# avr_g1000_ctr_24.net
KiCad netlist of a schematic drawn in EAGLE
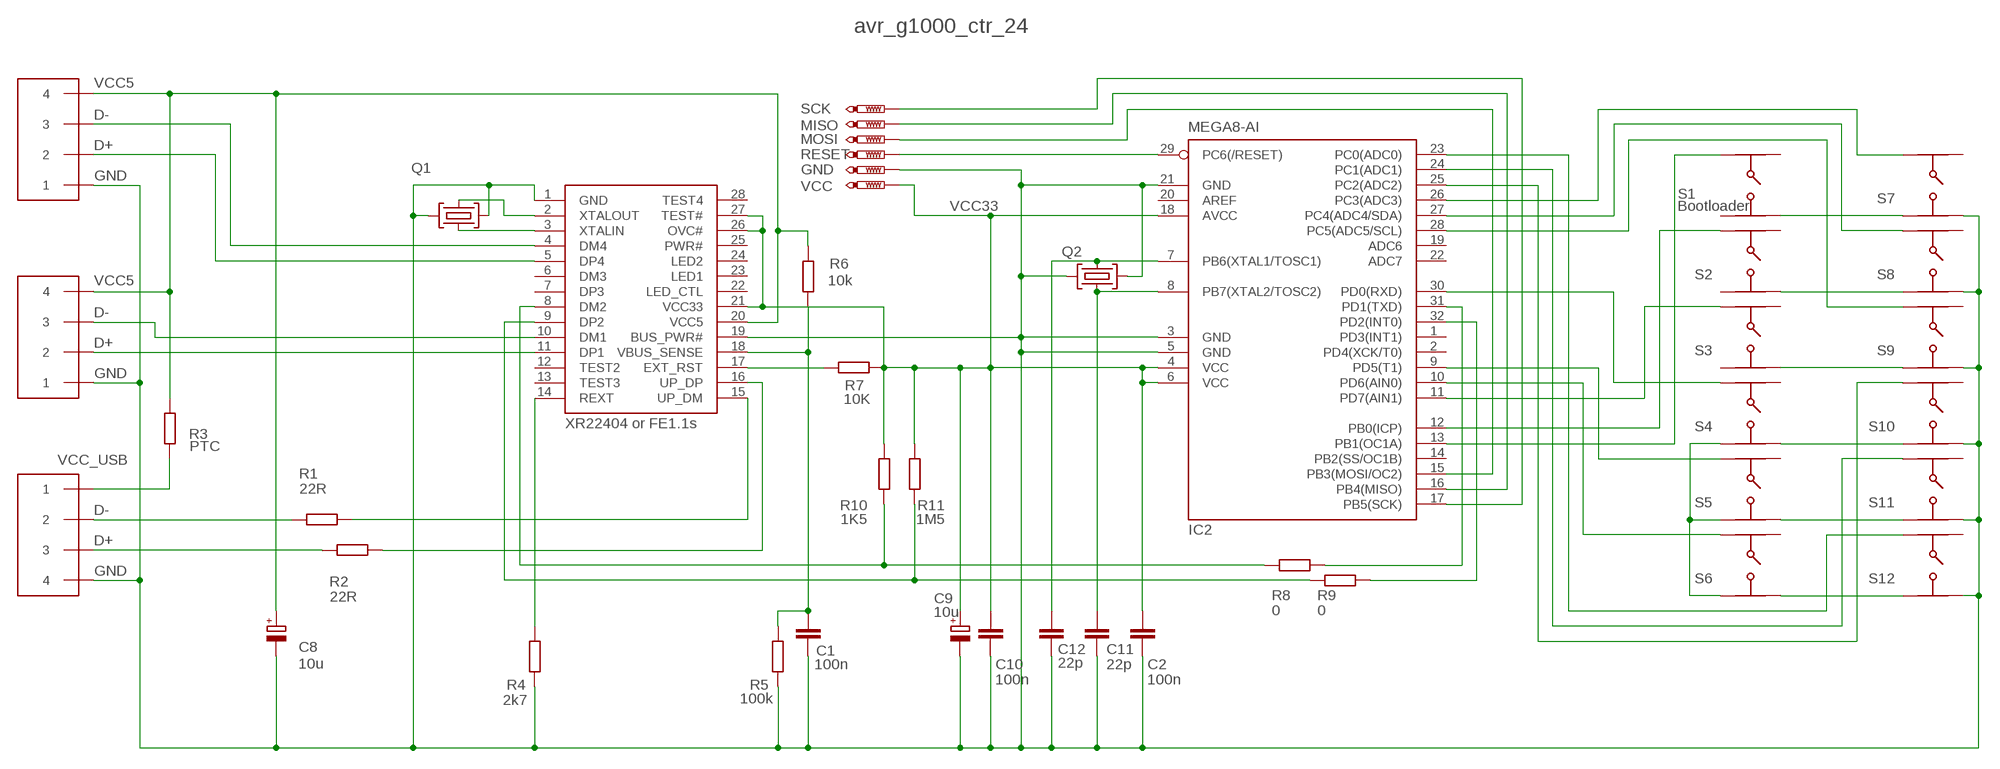
[diagram p0: schematic, sheet 1]

(export (version "E")
  (design (tool "Eeschema 10.0.6"))
  (components
    (comp (ref "C1")
      (value "100n")
      (footprint "eagle-import:C0402")
      (libsource (lib "eagle-import") (part "C-EUC0402"))
    )
    (comp (ref "C2")
      (value "100n")
      (footprint "eagle-import:C0402")
      (libsource (lib "eagle-import") (part "C-EUC0402"))
    )
    (comp (ref "C8")
      (value "10u")
      (footprint "eagle-import:SMC_A")
      (libsource (lib "eagle-import") (part "CPOL-EUSMCA"))
    )
    (comp (ref "C9")
      (value "10u")
      (footprint "eagle-import:SMC_A")
      (libsource (lib "eagle-import") (part "CPOL-EUSMCA"))
    )
    (comp (ref "C10")
      (value "100n")
      (footprint "eagle-import:C0402")
      (libsource (lib "eagle-import") (part "C-EUC0402"))
    )
    (comp (ref "C11")
      (value "22p")
      (footprint "eagle-import:C0402")
      (libsource (lib "eagle-import") (part "C-EUC0402"))
    )
    (comp (ref "C12")
      (value "22p")
      (footprint "eagle-import:C0402")
      (libsource (lib "eagle-import") (part "C-EUC0402"))
    )
    (comp (ref "GND")
      (value "PTR1TP10R")
      (footprint "eagle-import:TP10R")
      (libsource (lib "eagle-import") (part "PTR1TP10R"))
    )
    (comp (ref "IC2")
      (value "MEGA8-AI")
      (footprint "eagle-import:TQFP32-08")
      (fields (field (name "MPN") "ATMEGA8-16AU"))
      (libsource (lib "eagle-import") (part "MEGA8-AI"))
    )
    (comp (ref "MISO")
      (value "PTR1TP10R")
      (footprint "eagle-import:TP10R")
      (libsource (lib "eagle-import") (part "PTR1TP10R"))
    )
    (comp (ref "MOSI")
      (value "PTR1TP10R")
      (footprint "eagle-import:TP10R")
      (libsource (lib "eagle-import") (part "PTR1TP10R"))
    )
    (comp (ref "Q1")
      (value "12MHz")
      (footprint "eagle-import:OSCCC500X320X100")
      (libsource (lib "eagle-import") (part "MJ-CRYSTALMJ"))
    )
    (comp (ref "Q2")
      (value "12Mhz")
      (footprint "eagle-import:OSCCC500X320X100")
      (libsource (lib "eagle-import") (part "MJ-CRYSTALMJ"))
    )
    (comp (ref "R1")
      (value "22R")
      (footprint "eagle-import:R0603")
      (libsource (lib "eagle-import") (part "R-EU_R0603"))
    )
    (comp (ref "R2")
      (value "22R")
      (footprint "eagle-import:R0603")
      (libsource (lib "eagle-import") (part "R-EU_R0603"))
    )
    (comp (ref "R3")
      (value "PTC")
      (footprint "eagle-import:R0805")
      (libsource (lib "eagle-import") (part "R-EU_R0805"))
    )
    (comp (ref "R4")
      (value "2k7")
      (footprint "eagle-import:R0603")
      (libsource (lib "eagle-import") (part "R-EU_R0603"))
    )
    (comp (ref "R5")
      (value "100k")
      (footprint "eagle-import:R0603")
      (libsource (lib "eagle-import") (part "R-EU_R0603"))
    )
    (comp (ref "R6")
      (value "10k")
      (footprint "eagle-import:R0603")
      (libsource (lib "eagle-import") (part "R-EU_R0603"))
    )
    (comp (ref "R7")
      (value "10K")
      (footprint "eagle-import:R0603")
      (libsource (lib "eagle-import") (part "R-EU_R0603"))
    )
    (comp (ref "R8")
      (value "0")
      (footprint "eagle-import:R0603")
      (libsource (lib "eagle-import") (part "R-EU_R0603"))
    )
    (comp (ref "R9")
      (value "0")
      (footprint "eagle-import:R0603")
      (libsource (lib "eagle-import") (part "R-EU_R0603"))
    )
    (comp (ref "R10")
      (value "1K5")
      (footprint "eagle-import:R0603")
      (libsource (lib "eagle-import") (part "R-EU_R0603"))
    )
    (comp (ref "R11")
      (value "1M5")
      (footprint "eagle-import:R0603")
      (libsource (lib "eagle-import") (part "R-EU_R0603"))
    )
    (comp (ref "RESET")
      (value "PTR1TP10R")
      (footprint "eagle-import:TP10R")
      (libsource (lib "eagle-import") (part "PTR1TP10R"))
    )
    (comp (ref "S1")
      (value "B3FS1000")
      (footprint "eagle-import:B3FS1000")
      (libsource (lib "eagle-import") (part "B3FS1000"))
    )
    (comp (ref "S2")
      (value "B3FS1000")
      (footprint "eagle-import:B3FS1000")
      (libsource (lib "eagle-import") (part "B3FS1000"))
    )
    (comp (ref "S3")
      (value "B3FS1000")
      (footprint "eagle-import:B3FS1000")
      (libsource (lib "eagle-import") (part "B3FS1000"))
    )
    (comp (ref "S4")
      (value "B3FS1000")
      (footprint "eagle-import:B3FS1000")
      (libsource (lib "eagle-import") (part "B3FS1000"))
    )
    (comp (ref "S5")
      (value "B3FS1000")
      (footprint "eagle-import:B3FS1000")
      (libsource (lib "eagle-import") (part "B3FS1000"))
    )
    (comp (ref "S6")
      (value "B3FS1000")
      (footprint "eagle-import:B3FS1000")
      (libsource (lib "eagle-import") (part "B3FS1000"))
    )
    (comp (ref "S7")
      (value "B3FS1000")
      (footprint "eagle-import:B3FS1000")
      (libsource (lib "eagle-import") (part "B3FS1000"))
    )
    (comp (ref "S8")
      (value "B3FS1000")
      (footprint "eagle-import:B3FS1000")
      (libsource (lib "eagle-import") (part "B3FS1000"))
    )
    (comp (ref "S9")
      (value "B3FS1000")
      (footprint "eagle-import:B3FS1000")
      (libsource (lib "eagle-import") (part "B3FS1000"))
    )
    (comp (ref "S10")
      (value "B3FS1000")
      (footprint "eagle-import:B3FS1000")
      (libsource (lib "eagle-import") (part "B3FS1000"))
    )
    (comp (ref "S11")
      (value "B3FS1000")
      (footprint "eagle-import:B3FS1000")
      (libsource (lib "eagle-import") (part "B3FS1000"))
    )
    (comp (ref "S12")
      (value "B3FS1000")
      (footprint "eagle-import:B3FS1000")
      (libsource (lib "eagle-import") (part "B3FS1000"))
    )
    (comp (ref "SCK")
      (value "PTR1TP10R")
      (footprint "eagle-import:TP10R")
      (libsource (lib "eagle-import") (part "PTR1TP10R"))
    )
    (comp (ref "U$1")
      (value "HEADER4X1.27")
      (footprint "eagle-import:HEADER4X1.27")
      (libsource (lib "eagle-import") (part "HEADER4X1.27"))
    )
    (comp (ref "U$2")
      (value "HEADER4X1.27")
      (footprint "eagle-import:HEADER4X1.27")
      (libsource (lib "eagle-import") (part "HEADER4X1.27"))
    )
    (comp (ref "U$3")
      (value "HEADER4X1.27")
      (footprint "eagle-import:HEADER4X1.27")
      (libsource (lib "eagle-import") (part "HEADER4X1.27"))
    )
    (comp (ref "VCC")
      (value "PTR1TP10R")
      (footprint "eagle-import:TP10R")
      (libsource (lib "eagle-import") (part "PTR1TP10R"))
    )
    (comp (ref "XR22404")
      (value "XR22404")
      (footprint "eagle-import:XR22404")
      (libsource (lib "eagle-import") (part "XR22404"))
    )
  )
  (nets
    (net (code "1") (name "/D+") (class "Default")
      (node (ref "R2") (pin "1") (pinfunction "1_1") (pintype "passive"))
      (node (ref "U$1") (pin "P3") (pinfunction "3_P3") (pintype "bidirectional"))
    )
    (net (code "2") (name "/D-") (class "Default")
      (node (ref "R1") (pin "1") (pinfunction "1_1") (pintype "passive"))
      (node (ref "U$1") (pin "P2") (pinfunction "2_P2") (pintype "bidirectional"))
    )
    (net (code "3") (name "/GND") (class "Default")
      (node (ref "C1") (pin "2") (pinfunction "2_2") (pintype "passive"))
      (node (ref "C10") (pin "2") (pinfunction "2_2") (pintype "passive"))
      (node (ref "C11") (pin "2") (pinfunction "2_2") (pintype "passive"))
      (node (ref "C12") (pin "2") (pinfunction "2_2") (pintype "passive"))
      (node (ref "C2") (pin "2") (pinfunction "2_2") (pintype "passive"))
      (node (ref "C8") (pin "-") (pinfunction "-_-") (pintype "passive"))
      (node (ref "C9") (pin "-") (pinfunction "-_-") (pintype "passive"))
      (node (ref "GND") (pin "TP") (pinfunction "TP_TP") (pintype "input"))
      (node (ref "IC2") (pin "21") (pinfunction "GND_21") (pintype "power_in"))
      (node (ref "IC2") (pin "3") (pinfunction "GND_3") (pintype "power_in"))
      (node (ref "IC2") (pin "5") (pinfunction "GND_5") (pintype "power_in"))
      (node (ref "Q1") (pin "2") (pinfunction "GND1_2") (pintype "bidirectional"))
      (node (ref "Q1") (pin "4") (pinfunction "GND2_4") (pintype "bidirectional"))
      (node (ref "Q2") (pin "2") (pinfunction "GND1_2") (pintype "bidirectional"))
      (node (ref "Q2") (pin "4") (pinfunction "GND2_4") (pintype "bidirectional"))
      (node (ref "R4") (pin "1") (pinfunction "1_1") (pintype "passive"))
      (node (ref "R5") (pin "1") (pinfunction "1_1") (pintype "passive"))
      (node (ref "S1") (pin "1") (pinfunction "1_1") (pintype "passive"))
      (node (ref "S10") (pin "1") (pinfunction "1_1") (pintype "passive"))
      (node (ref "S10") (pin "2") (pinfunction "2_2") (pintype "passive"))
      (node (ref "S11") (pin "1") (pinfunction "1_1") (pintype "passive"))
      (node (ref "S11") (pin "2") (pinfunction "2_2") (pintype "passive"))
      (node (ref "S12") (pin "1") (pinfunction "1_1") (pintype "passive"))
      (node (ref "S12") (pin "2") (pinfunction "2_2") (pintype "passive"))
      (node (ref "S2") (pin "1") (pinfunction "1_1") (pintype "passive"))
      (node (ref "S3") (pin "1") (pinfunction "1_1") (pintype "passive"))
      (node (ref "S4") (pin "1") (pinfunction "1_1") (pintype "passive"))
      (node (ref "S4") (pin "2") (pinfunction "2_2") (pintype "passive"))
      (node (ref "S5") (pin "1") (pinfunction "1_1") (pintype "passive"))
      (node (ref "S5") (pin "2") (pinfunction "2_2") (pintype "passive"))
      (node (ref "S6") (pin "1") (pinfunction "1_1") (pintype "passive"))
      (node (ref "S6") (pin "2") (pinfunction "2_2") (pintype "passive"))
      (node (ref "S7") (pin "1") (pinfunction "1_1") (pintype "passive"))
      (node (ref "S7") (pin "2") (pinfunction "2_2") (pintype "passive"))
      (node (ref "S8") (pin "1") (pinfunction "1_1") (pintype "passive"))
      (node (ref "S8") (pin "2") (pinfunction "2_2") (pintype "passive"))
      (node (ref "S9") (pin "1") (pinfunction "1_1") (pintype "passive"))
      (node (ref "S9") (pin "2") (pinfunction "2_2") (pintype "passive"))
      (node (ref "U$1") (pin "P4") (pinfunction "4_P4") (pintype "bidirectional"))
      (node (ref "U$2") (pin "P1") (pinfunction "1_P1") (pintype "bidirectional"))
      (node (ref "U$3") (pin "P1") (pinfunction "1_P1") (pintype "bidirectional"))
      (node (ref "XR22404") (pin "1") (pinfunction "GND_1") (pintype "passive"))
      (node (ref "XR22404") (pin "19") (pinfunction "BUS_PWR#_19") (pintype "bidirectional"))
    )
    (net (code "4") (name "/VCC5") (class "Default")
      (node (ref "C8") (pin "+") (pinfunction "+_+") (pintype "passive"))
      (node (ref "R3") (pin "2") (pinfunction "2_2") (pintype "passive"))
      (node (ref "R6") (pin "2") (pinfunction "2_2") (pintype "passive"))
      (node (ref "U$2") (pin "P4") (pinfunction "4_P4") (pintype "bidirectional"))
      (node (ref "U$3") (pin "P4") (pinfunction "4_P4") (pintype "bidirectional"))
      (node (ref "XR22404") (pin "20") (pinfunction "VCC5_20") (pintype "bidirectional"))
    )
    (net (code "5") (name "/VCC33") (class "Default")
      (node (ref "C10") (pin "1") (pinfunction "1_1") (pintype "passive"))
      (node (ref "C2") (pin "1") (pinfunction "1_1") (pintype "passive"))
      (node (ref "C9") (pin "+") (pinfunction "+_+") (pintype "passive"))
      (node (ref "IC2") (pin "18") (pinfunction "AVCC_18") (pintype "power_in"))
      (node (ref "IC2") (pin "4") (pinfunction "VCC_4") (pintype "power_in"))
      (node (ref "IC2") (pin "6") (pinfunction "VCC_6") (pintype "power_in"))
      (node (ref "R10") (pin "2") (pinfunction "2_2") (pintype "passive"))
      (node (ref "R11") (pin "2") (pinfunction "2_2") (pintype "passive"))
      (node (ref "R7") (pin "2") (pinfunction "2_2") (pintype "passive"))
      (node (ref "VCC") (pin "TP") (pinfunction "TP_TP") (pintype "input"))
      (node (ref "XR22404") (pin "21") (pinfunction "VCC33_21") (pintype "bidirectional"))
      (node (ref "XR22404") (pin "26") (pinfunction "OVC#_26") (pintype "bidirectional"))
      (node (ref "XR22404") (pin "27") (pinfunction "TEST#_27") (pintype "bidirectional"))
    )
    (net (code "6") (name "/VCC_USB") (class "Default")
      (node (ref "R3") (pin "1") (pinfunction "1_1") (pintype "passive"))
      (node (ref "U$1") (pin "P1") (pinfunction "1_P1") (pintype "bidirectional"))
    )
    (net (code "7") (name "Net-(IC2-PB0(ICP))") (class "Default")
      (node (ref "IC2") (pin "12") (pinfunction "PB0(ICP)_12") (pintype "bidirectional"))
      (node (ref "S2") (pin "4") (pinfunction "4_4") (pintype "passive"))
    )
    (net (code "8") (name "Net-(IC2-PB1(OC1A))") (class "Default")
      (node (ref "IC2") (pin "13") (pinfunction "PB1(OC1A)_13") (pintype "bidirectional"))
      (node (ref "S1") (pin "4") (pinfunction "4_4") (pintype "passive"))
    )
    (net (code "9") (name "Net-(IC2-PB3(MOSI{slash}OC2))") (class "Default")
      (node (ref "IC2") (pin "15") (pinfunction "PB3(MOSI/OC2)_15") (pintype "bidirectional"))
      (node (ref "MOSI") (pin "TP") (pinfunction "TP_TP") (pintype "input"))
    )
    (net (code "10") (name "Net-(IC2-PB4(MISO))") (class "Default")
      (node (ref "IC2") (pin "16") (pinfunction "PB4(MISO)_16") (pintype "bidirectional"))
      (node (ref "MISO") (pin "TP") (pinfunction "TP_TP") (pintype "input"))
    )
    (net (code "11") (name "Net-(IC2-PB5(SCK))") (class "Default")
      (node (ref "IC2") (pin "17") (pinfunction "PB5(SCK)_17") (pintype "bidirectional"))
      (node (ref "SCK") (pin "TP") (pinfunction "TP_TP") (pintype "input"))
    )
    (net (code "12") (name "Net-(IC2-PB6(XTAL1{slash}TOSC1))") (class "Default")
      (node (ref "C12") (pin "1") (pinfunction "1_1") (pintype "passive"))
      (node (ref "IC2") (pin "7") (pinfunction "PB6(XTAL1/TOSC1)_7") (pintype "bidirectional"))
      (node (ref "Q2") (pin "1") (pinfunction "CRYSTAL1_1") (pintype "bidirectional"))
    )
    (net (code "13") (name "Net-(IC2-PB7(XTAL2{slash}TOSC2))") (class "Default")
      (node (ref "C11") (pin "1") (pinfunction "1_1") (pintype "passive"))
      (node (ref "IC2") (pin "8") (pinfunction "PB7(XTAL2/TOSC2)_8") (pintype "bidirectional"))
      (node (ref "Q2") (pin "3") (pinfunction "CRYSTAL2_3") (pintype "bidirectional"))
    )
    (net (code "14") (name "Net-(IC2-PC0(ADC0))") (class "Default")
      (node (ref "IC2") (pin "23") (pinfunction "PC0(ADC0)_23") (pintype "bidirectional"))
      (node (ref "S12") (pin "4") (pinfunction "4_4") (pintype "passive"))
    )
    (net (code "15") (name "Net-(IC2-PC1(ADC1))") (class "Default")
      (node (ref "IC2") (pin "24") (pinfunction "PC1(ADC1)_24") (pintype "bidirectional"))
      (node (ref "S11") (pin "4") (pinfunction "4_4") (pintype "passive"))
    )
    (net (code "16") (name "Net-(IC2-PC2(ADC2))") (class "Default")
      (node (ref "IC2") (pin "25") (pinfunction "PC2(ADC2)_25") (pintype "bidirectional"))
      (node (ref "S10") (pin "4") (pinfunction "4_4") (pintype "passive"))
    )
    (net (code "17") (name "Net-(IC2-PC3(ADC3))") (class "Default")
      (node (ref "IC2") (pin "26") (pinfunction "PC3(ADC3)_26") (pintype "bidirectional"))
      (node (ref "S7") (pin "4") (pinfunction "4_4") (pintype "passive"))
    )
    (net (code "18") (name "Net-(IC2-PC4(ADC4{slash}SDA))") (class "Default")
      (node (ref "IC2") (pin "27") (pinfunction "PC4(ADC4/SDA)_27") (pintype "bidirectional"))
      (node (ref "S8") (pin "4") (pinfunction "4_4") (pintype "passive"))
    )
    (net (code "19") (name "Net-(IC2-PC5(ADC5{slash}SCL))") (class "Default")
      (node (ref "IC2") (pin "28") (pinfunction "PC5(ADC5/SCL)_28") (pintype "bidirectional"))
      (node (ref "S9") (pin "4") (pinfunction "4_4") (pintype "passive"))
    )
    (net (code "20") (name "Net-(IC2-PC6({slash}RESET))") (class "Default")
      (node (ref "IC2") (pin "29") (pinfunction "PC6(/RESET)_29") (pintype "bidirectional"))
      (node (ref "RESET") (pin "TP") (pinfunction "TP_TP") (pintype "input"))
    )
    (net (code "21") (name "Net-(IC2-PD0(RXD))") (class "Default")
      (node (ref "IC2") (pin "30") (pinfunction "PD0(RXD)_30") (pintype "bidirectional"))
      (node (ref "S4") (pin "4") (pinfunction "4_4") (pintype "passive"))
    )
    (net (code "22") (name "Net-(IC2-PD1(TXD))") (class "Default")
      (node (ref "IC2") (pin "31") (pinfunction "PD1(TXD)_31") (pintype "bidirectional"))
      (node (ref "R8") (pin "2") (pinfunction "2_2") (pintype "passive"))
    )
    (net (code "23") (name "Net-(IC2-PD2(INT0))") (class "Default")
      (node (ref "IC2") (pin "32") (pinfunction "PD2(INT0)_32") (pintype "bidirectional"))
      (node (ref "R9") (pin "2") (pinfunction "2_2") (pintype "passive"))
    )
    (net (code "24") (name "Net-(IC2-PD5(T1))") (class "Default")
      (node (ref "IC2") (pin "9") (pinfunction "PD5(T1)_9") (pintype "bidirectional"))
      (node (ref "S5") (pin "4") (pinfunction "4_4") (pintype "passive"))
    )
    (net (code "25") (name "Net-(IC2-PD6(AIN0))") (class "Default")
      (node (ref "IC2") (pin "10") (pinfunction "PD6(AIN0)_10") (pintype "bidirectional"))
      (node (ref "S6") (pin "4") (pinfunction "4_4") (pintype "passive"))
    )
    (net (code "26") (name "Net-(IC2-PD7(AIN1))") (class "Default")
      (node (ref "IC2") (pin "11") (pinfunction "PD7(AIN1)_11") (pintype "bidirectional"))
      (node (ref "S3") (pin "4") (pinfunction "4_4") (pintype "passive"))
    )
    (net (code "27") (name "Net-(Q1-CRYSTAL1)") (class "Default")
      (node (ref "Q1") (pin "1") (pinfunction "CRYSTAL1_1") (pintype "bidirectional"))
      (node (ref "XR22404") (pin "2") (pinfunction "XTALOUT_2") (pintype "bidirectional"))
    )
    (net (code "28") (name "Net-(Q1-CRYSTAL2)") (class "Default")
      (node (ref "Q1") (pin "3") (pinfunction "CRYSTAL2_3") (pintype "bidirectional"))
      (node (ref "XR22404") (pin "3") (pinfunction "XTALIN_3") (pintype "bidirectional"))
    )
    (net (code "29") (name "Net-(U$2-2)") (class "Default")
      (node (ref "U$2") (pin "P2") (pinfunction "2_P2") (pintype "bidirectional"))
      (node (ref "XR22404") (pin "11") (pinfunction "DP1_11") (pintype "bidirectional"))
    )
    (net (code "30") (name "Net-(U$2-3)") (class "Default")
      (node (ref "U$2") (pin "P3") (pinfunction "3_P3") (pintype "bidirectional"))
      (node (ref "XR22404") (pin "10") (pinfunction "DM1_10") (pintype "bidirectional"))
    )
    (net (code "31") (name "Net-(U$3-2)") (class "Default")
      (node (ref "U$3") (pin "P2") (pinfunction "2_P2") (pintype "bidirectional"))
      (node (ref "XR22404") (pin "5") (pinfunction "DP4_5") (pintype "bidirectional"))
    )
    (net (code "32") (name "Net-(U$3-3)") (class "Default")
      (node (ref "U$3") (pin "P3") (pinfunction "3_P3") (pintype "bidirectional"))
      (node (ref "XR22404") (pin "4") (pinfunction "DM4_4") (pintype "bidirectional"))
    )
    (net (code "33") (name "Net-(XR22404-DM2)") (class "Default")
      (node (ref "R10") (pin "1") (pinfunction "1_1") (pintype "passive"))
      (node (ref "R8") (pin "1") (pinfunction "1_1") (pintype "passive"))
      (node (ref "XR22404") (pin "8") (pinfunction "DM2_8") (pintype "bidirectional"))
    )
    (net (code "34") (name "Net-(XR22404-DP2)") (class "Default")
      (node (ref "R11") (pin "1") (pinfunction "1_1") (pintype "passive"))
      (node (ref "R9") (pin "1") (pinfunction "1_1") (pintype "passive"))
      (node (ref "XR22404") (pin "9") (pinfunction "DP2_9") (pintype "bidirectional"))
    )
    (net (code "35") (name "Net-(XR22404-EXT_RST)") (class "Default")
      (node (ref "R7") (pin "1") (pinfunction "1_1") (pintype "passive"))
      (node (ref "XR22404") (pin "17") (pinfunction "EXT_RST_17") (pintype "bidirectional"))
    )
    (net (code "36") (name "Net-(XR22404-REXT)") (class "Default")
      (node (ref "R4") (pin "2") (pinfunction "2_2") (pintype "passive"))
      (node (ref "XR22404") (pin "14") (pinfunction "REXT_14") (pintype "bidirectional"))
    )
    (net (code "37") (name "Net-(XR22404-UP_DM)") (class "Default")
      (node (ref "R1") (pin "2") (pinfunction "2_2") (pintype "passive"))
      (node (ref "XR22404") (pin "15") (pinfunction "UP_DM_15") (pintype "bidirectional"))
    )
    (net (code "38") (name "Net-(XR22404-UP_DP)") (class "Default")
      (node (ref "R2") (pin "2") (pinfunction "2_2") (pintype "passive"))
      (node (ref "XR22404") (pin "16") (pinfunction "UP_DP_16") (pintype "bidirectional"))
    )
    (net (code "39") (name "Net-(XR22404-VBUS_SENSE)") (class "Default")
      (node (ref "C1") (pin "1") (pinfunction "1_1") (pintype "passive"))
      (node (ref "R5") (pin "2") (pinfunction "2_2") (pintype "passive"))
      (node (ref "R6") (pin "1") (pinfunction "1_1") (pintype "passive"))
      (node (ref "XR22404") (pin "18") (pinfunction "VBUS_SENSE_18") (pintype "bidirectional"))
    )
    (net (code "40") (name "unconnected-(IC2-ADC6-Pad19)") (class "Default")
      (node (ref "IC2") (pin "19") (pinfunction "ADC6_19") (pintype "bidirectional"))
    )
    (net (code "41") (name "unconnected-(IC2-ADC7-Pad22)") (class "Default")
      (node (ref "IC2") (pin "22") (pinfunction "ADC7_22") (pintype "bidirectional"))
    )
    (net (code "42") (name "unconnected-(IC2-AREF-Pad20)") (class "Default")
      (node (ref "IC2") (pin "20") (pinfunction "AREF_20") (pintype "passive"))
    )
    (net (code "43") (name "unconnected-(IC2-PB2(SS{slash}OC1B)-Pad14)") (class "Default")
      (node (ref "IC2") (pin "14") (pinfunction "PB2(SS/OC1B)_14") (pintype "bidirectional"))
    )
    (net (code "44") (name "unconnected-(IC2-PD3(INT1)-Pad1)") (class "Default")
      (node (ref "IC2") (pin "1") (pinfunction "PD3(INT1)_1") (pintype "bidirectional"))
    )
    (net (code "45") (name "unconnected-(IC2-PD4(XCK{slash}T0)-Pad2)") (class "Default")
      (node (ref "IC2") (pin "2") (pinfunction "PD4(XCK/T0)_2") (pintype "bidirectional"))
    )
    (net (code "46") (name "unconnected-(S1-Pad2)") (class "Default")
      (node (ref "S1") (pin "2") (pinfunction "2_2") (pintype "passive"))
    )
    (net (code "47") (name "unconnected-(S1-Pad3)") (class "Default")
      (node (ref "S1") (pin "3") (pinfunction "3_3") (pintype "passive"))
    )
    (net (code "48") (name "unconnected-(S2-Pad2)") (class "Default")
      (node (ref "S2") (pin "2") (pinfunction "2_2") (pintype "passive"))
    )
    (net (code "49") (name "unconnected-(S2-Pad3)") (class "Default")
      (node (ref "S2") (pin "3") (pinfunction "3_3") (pintype "passive"))
    )
    (net (code "50") (name "unconnected-(S3-Pad2)") (class "Default")
      (node (ref "S3") (pin "2") (pinfunction "2_2") (pintype "passive"))
    )
    (net (code "51") (name "unconnected-(S3-Pad3)") (class "Default")
      (node (ref "S3") (pin "3") (pinfunction "3_3") (pintype "passive"))
    )
    (net (code "52") (name "unconnected-(S4-Pad3)") (class "Default")
      (node (ref "S4") (pin "3") (pinfunction "3_3") (pintype "passive"))
    )
    (net (code "53") (name "unconnected-(S5-Pad3)") (class "Default")
      (node (ref "S5") (pin "3") (pinfunction "3_3") (pintype "passive"))
    )
    (net (code "54") (name "unconnected-(S6-Pad3)") (class "Default")
      (node (ref "S6") (pin "3") (pinfunction "3_3") (pintype "passive"))
    )
    (net (code "55") (name "unconnected-(S7-Pad3)") (class "Default")
      (node (ref "S7") (pin "3") (pinfunction "3_3") (pintype "passive"))
    )
    (net (code "56") (name "unconnected-(S8-Pad3)") (class "Default")
      (node (ref "S8") (pin "3") (pinfunction "3_3") (pintype "passive"))
    )
    (net (code "57") (name "unconnected-(S9-Pad3)") (class "Default")
      (node (ref "S9") (pin "3") (pinfunction "3_3") (pintype "passive"))
    )
    (net (code "58") (name "unconnected-(S10-Pad3)") (class "Default")
      (node (ref "S10") (pin "3") (pinfunction "3_3") (pintype "passive"))
    )
    (net (code "59") (name "unconnected-(S11-Pad3)") (class "Default")
      (node (ref "S11") (pin "3") (pinfunction "3_3") (pintype "passive"))
    )
    (net (code "60") (name "unconnected-(S12-Pad3)") (class "Default")
      (node (ref "S12") (pin "3") (pinfunction "3_3") (pintype "passive"))
    )
    (net (code "61") (name "unconnected-(XR22404-DM3-Pad6)") (class "Default")
      (node (ref "XR22404") (pin "6") (pinfunction "DM3_6") (pintype "bidirectional"))
    )
    (net (code "62") (name "unconnected-(XR22404-DP3-Pad7)") (class "Default")
      (node (ref "XR22404") (pin "7") (pinfunction "DP3_7") (pintype "bidirectional"))
    )
    (net (code "63") (name "unconnected-(XR22404-LED1-Pad23)") (class "Default")
      (node (ref "XR22404") (pin "23") (pinfunction "LED1_23") (pintype "bidirectional"))
    )
    (net (code "64") (name "unconnected-(XR22404-LED2-Pad24)") (class "Default")
      (node (ref "XR22404") (pin "24") (pinfunction "LED2_24") (pintype "bidirectional"))
    )
    (net (code "65") (name "unconnected-(XR22404-LED_CTL-Pad22)") (class "Default")
      (node (ref "XR22404") (pin "22") (pinfunction "LED_CTL_22") (pintype "bidirectional"))
    )
    (net (code "66") (name "unconnected-(XR22404-PWR#-Pad25)") (class "Default")
      (node (ref "XR22404") (pin "25") (pinfunction "PWR#_25") (pintype "bidirectional"))
    )
    (net (code "67") (name "unconnected-(XR22404-TEST2-Pad12)") (class "Default")
      (node (ref "XR22404") (pin "12") (pinfunction "TEST2_12") (pintype "bidirectional"))
    )
    (net (code "68") (name "unconnected-(XR22404-TEST3-Pad13)") (class "Default")
      (node (ref "XR22404") (pin "13") (pinfunction "TEST3_13") (pintype "bidirectional"))
    )
    (net (code "69") (name "unconnected-(XR22404-TEST4-Pad28)") (class "Default")
      (node (ref "XR22404") (pin "28") (pinfunction "TEST4_28") (pintype "bidirectional"))
    )
  )
)
